# odessa_rev_A.net
KiCad netlist of a schematic drawn in EAGLE
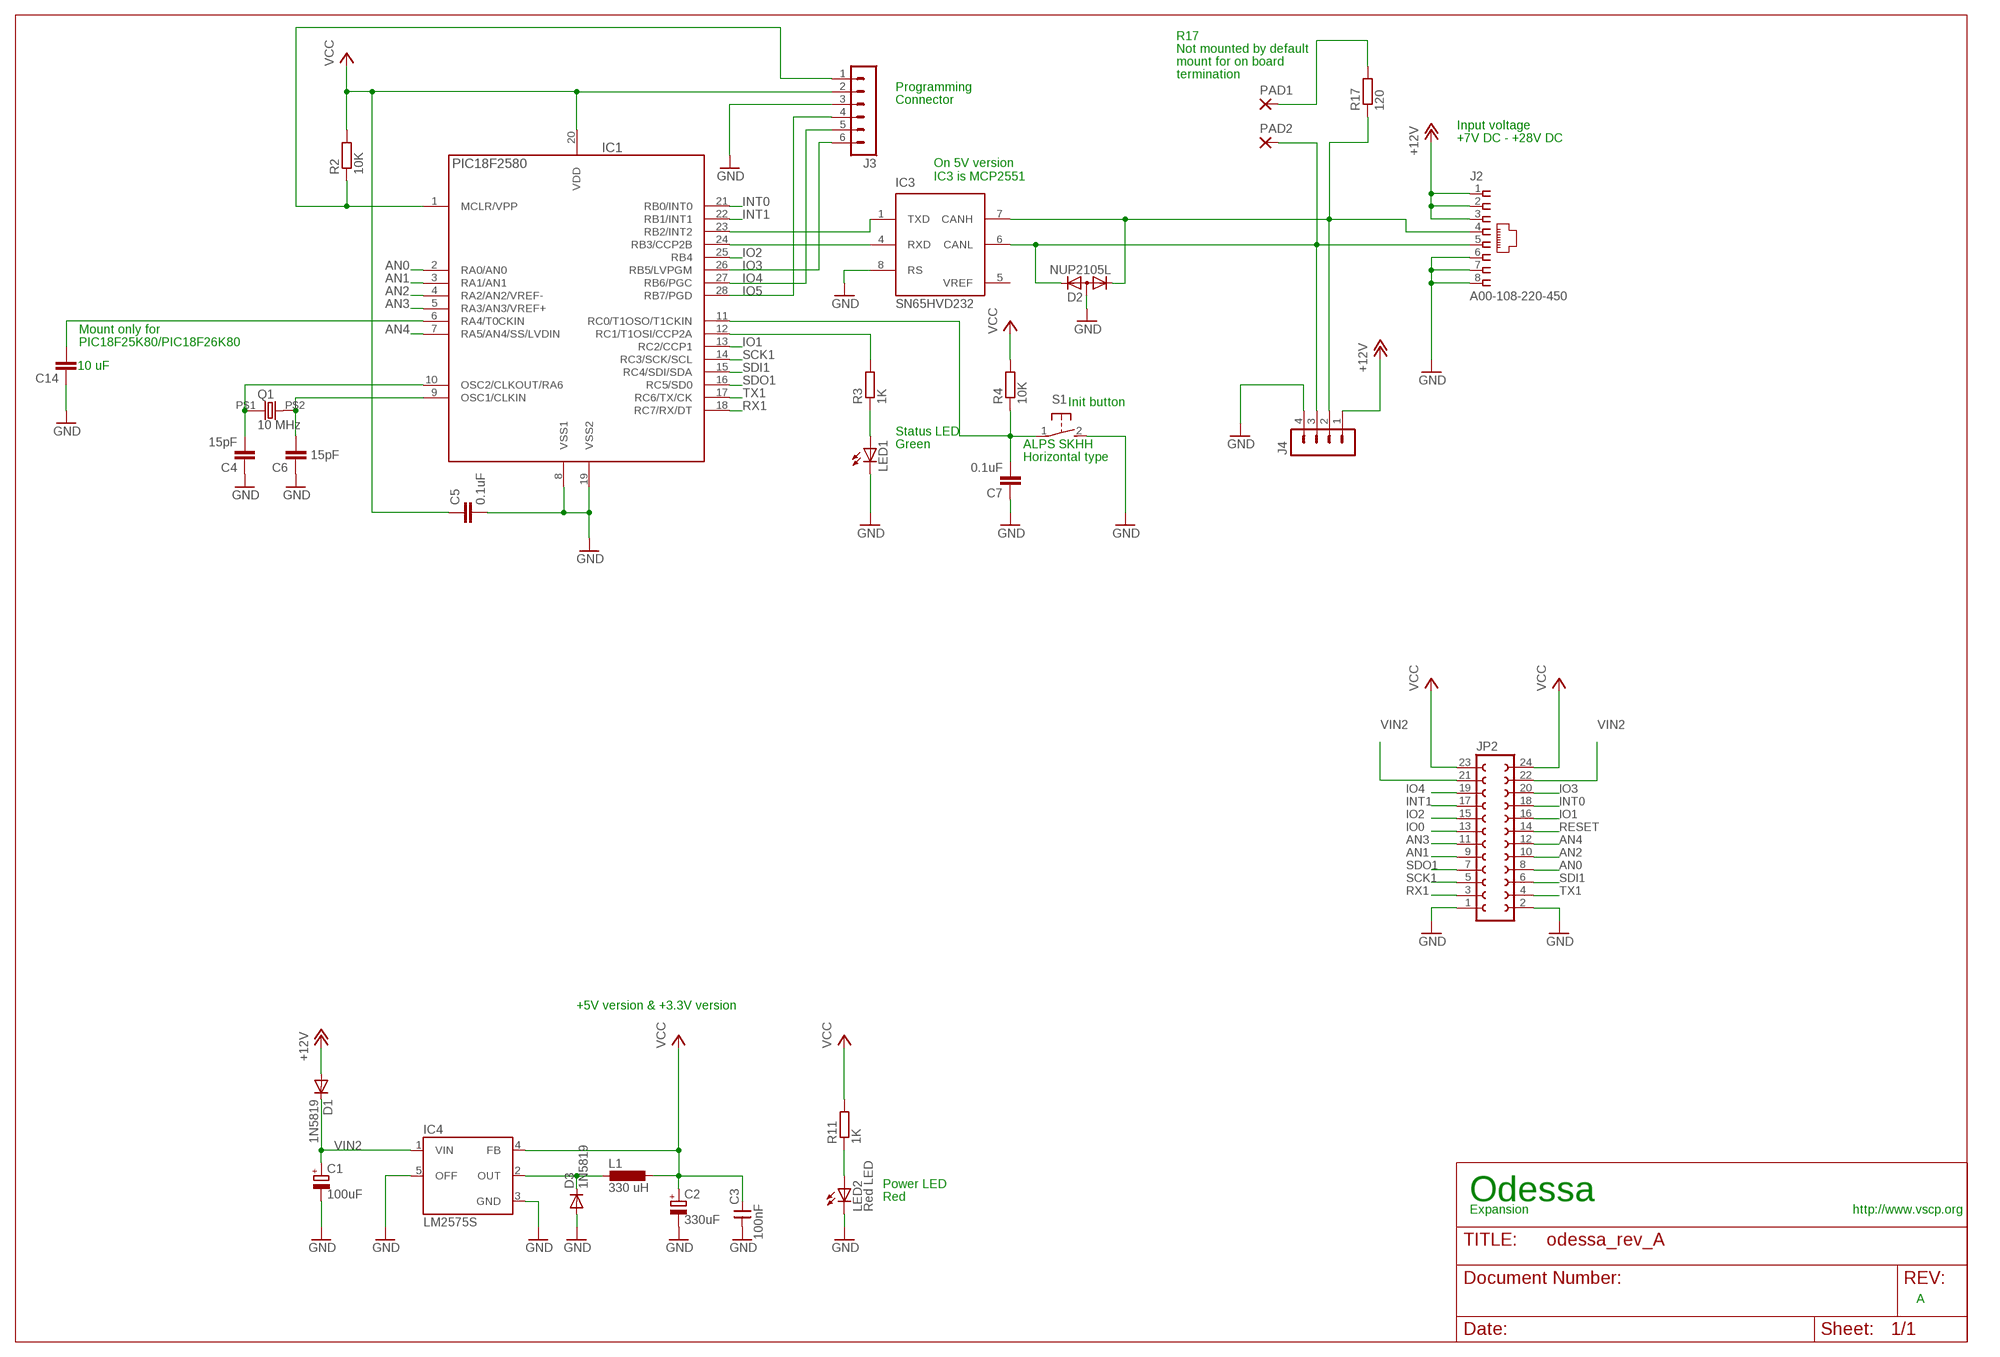
[diagram p0: schematic, sheet 1]

(export (version "E")
  (design (tool "Eeschema 10.0.6"))
  (components
    (comp (ref "C1")
      (value "100uF")
      (footprint "eagle-import:PANASONIC_D")
      (libsource (lib "eagle-import") (part "CPOL-EUD"))
    )
    (comp (ref "C2")
      (value "330uF")
      (footprint "eagle-import:PANASONIC_D")
      (libsource (lib "eagle-import") (part "CPOL-EUD"))
    )
    (comp (ref "C3")
      (value "100nF")
      (footprint "eagle-import:0805")
      (libsource (lib "eagle-import") (part "CNP-0805"))
    )
    (comp (ref "C4")
      (value "15pF")
      (footprint "eagle-import:C0805")
      (libsource (lib "eagle-import") (part "C-EUC0805"))
    )
    (comp (ref "C5")
      (value "0.1uF")
      (footprint "eagle-import:C0805")
      (libsource (lib "eagle-import") (part "C-EUC0805"))
    )
    (comp (ref "C6")
      (value "15pF")
      (footprint "eagle-import:C0805")
      (libsource (lib "eagle-import") (part "C-EUC0805"))
    )
    (comp (ref "C7")
      (value "0.1uF")
      (footprint "eagle-import:C0805")
      (libsource (lib "eagle-import") (part "C-EUC0805"))
    )
    (comp (ref "C14")
      (value "10 uF")
      (footprint "eagle-import:C0805")
      (libsource (lib "eagle-import") (part "C-EUC0805"))
    )
    (comp (ref "D1")
      (value "1N5819")
      (footprint "eagle-import:SOD123")
      (libsource (lib "eagle-import") (part "DIODE-SOD123"))
    )
    (comp (ref "D2")
      (value "NUP2105L")
      (footprint "eagle-import:SOT23")
      (libsource (lib "eagle-import") (part "DIODE-2CA|ACSOT23"))
    )
    (comp (ref "D3")
      (value "1N5819")
      (footprint "eagle-import:SOD123")
      (libsource (lib "eagle-import") (part "DIODE-SOD123"))
    )
    (comp (ref "IC1")
      (value "PIC18F2580")
      (footprint "eagle-import:SO28")
      (libsource (lib "eagle-import") (part "PIC18F252-?I/SOL"))
    )
    (comp (ref "IC3")
      (value "SN65HVD232")
      (footprint "eagle-import:SO-08")
      (libsource (lib "eagle-import") (part "MCP2551SN"))
    )
    (comp (ref "IC4")
      (value "LM2575S")
      (footprint "eagle-import:TO263-5")
      (libsource (lib "eagle-import") (part "LM2575S"))
    )
    (comp (ref "J2")
      (value "A00-108-220-450")
      (footprint "eagle-import:RJ-45")
      (libsource (lib "eagle-import") (part "A00-108-220-450"))
    )
    (comp (ref "J3")
      (value "MA06-1")
      (footprint "eagle-import:MA06-1")
      (libsource (lib "eagle-import") (part "MA06-1"))
    )
    (comp (ref "J4")
      (value "MA04-1")
      (footprint "eagle-import:MA04-1")
      (libsource (lib "eagle-import") (part "MA04-1"))
    )
    (comp (ref "JP2")
      (value "FE12-2")
      (footprint "eagle-import:FE12-2")
      (libsource (lib "eagle-import") (part "FE12-2"))
    )
    (comp (ref "L1")
      (value "330 uH")
      (footprint "eagle-import:DO3316P")
      (libsource (lib "eagle-import") (part "DO3316P"))
    )
    (comp (ref "LED1")
      (value "LEDCHIP-LED0805")
      (footprint "eagle-import:CHIP-LED0805")
      (libsource (lib "eagle-import") (part "LEDCHIP-LED0805"))
    )
    (comp (ref "LED2")
      (value "Red LED")
      (footprint "eagle-import:CHIP-LED0805")
      (libsource (lib "eagle-import") (part "LEDCHIP-LED0805"))
    )
    (comp (ref "PAD1")
      (value "1,6/0,8")
      (footprint "eagle-import:1,6_0,8")
      (libsource (lib "eagle-import") (part "1,6/0,8"))
    )
    (comp (ref "PAD2")
      (value "1,6/0,8")
      (footprint "eagle-import:1,6_0,8")
      (libsource (lib "eagle-import") (part "1,6/0,8"))
    )
    (comp (ref "Q1")
      (value "10 MHz")
      (footprint "eagle-import:9C")
      (libsource (lib "eagle-import") (part "HC-49S"))
    )
    (comp (ref "R2")
      (value "10K")
      (footprint "eagle-import:R0805")
      (libsource (lib "eagle-import") (part "R-EU_R0805"))
    )
    (comp (ref "R3")
      (value "1K")
      (footprint "eagle-import:R0805")
      (libsource (lib "eagle-import") (part "R-EU_R0805"))
    )
    (comp (ref "R4")
      (value "10K")
      (footprint "eagle-import:R0805")
      (libsource (lib "eagle-import") (part "R-EU_R0805"))
    )
    (comp (ref "R11")
      (value "1K")
      (footprint "eagle-import:R0805")
      (libsource (lib "eagle-import") (part "R-EU_R0805"))
    )
    (comp (ref "R17")
      (value "120")
      (footprint "eagle-import:R0805")
      (libsource (lib "eagle-import") (part "R-EU_R0805"))
    )
    (comp (ref "S1")
      (value "31-XX")
      (footprint "eagle-import:B3F-31XX")
      (fields (field (name "MPN") "B3F-3100"))
      (libsource (lib "eagle-import") (part "31-XX"))
    )
  )
  (nets
    (net (code "1") (name "+12V") (class "Default")
      (node (ref "D1") (pin "A") (pinfunction "A_A") (pintype "passive"))
      (node (ref "J2") (pin "1") (pinfunction "1_1") (pintype "passive"))
      (node (ref "J2") (pin "2") (pinfunction "2_2") (pintype "passive"))
      (node (ref "J2") (pin "3") (pinfunction "3_3") (pintype "passive"))
      (node (ref "J4") (pin "1") (pinfunction "1_1") (pintype "passive"))
    )
    (net (code "2") (name "/AN0") (class "Default")
      (node (ref "IC1") (pin "2") (pinfunction "RA0/AN0_2") (pintype "bidirectional"))
      (node (ref "JP2") (pin "8") (pinfunction "8_8") (pintype "passive"))
    )
    (net (code "3") (name "/AN1") (class "Default")
      (node (ref "IC1") (pin "3") (pinfunction "RA1/AN1_3") (pintype "bidirectional"))
      (node (ref "JP2") (pin "9") (pinfunction "9_9") (pintype "passive"))
    )
    (net (code "4") (name "/AN2") (class "Default")
      (node (ref "IC1") (pin "4") (pinfunction "RA2/AN2/VREF-_4") (pintype "bidirectional"))
      (node (ref "JP2") (pin "10") (pinfunction "10_10") (pintype "passive"))
    )
    (net (code "5") (name "/AN3") (class "Default")
      (node (ref "IC1") (pin "5") (pinfunction "RA3/AN3/VREF+_5") (pintype "bidirectional"))
      (node (ref "JP2") (pin "11") (pinfunction "11_11") (pintype "passive"))
    )
    (net (code "6") (name "/AN4") (class "Default")
      (node (ref "IC1") (pin "7") (pinfunction "RA5/AN4/SS/LVDIN_7") (pintype "bidirectional"))
      (node (ref "JP2") (pin "12") (pinfunction "12_12") (pintype "passive"))
    )
    (net (code "7") (name "/INT0") (class "Default")
      (node (ref "IC1") (pin "21") (pinfunction "RB0/INT0_21") (pintype "bidirectional"))
      (node (ref "JP2") (pin "18") (pinfunction "18_18") (pintype "passive"))
    )
    (net (code "8") (name "/INT1") (class "Default")
      (node (ref "IC1") (pin "22") (pinfunction "RB1/INT1_22") (pintype "bidirectional"))
      (node (ref "JP2") (pin "17") (pinfunction "17_17") (pintype "passive"))
    )
    (net (code "9") (name "/IO0") (class "Default")
      (node (ref "JP2") (pin "13") (pinfunction "13_13") (pintype "passive"))
    )
    (net (code "10") (name "/IO1") (class "Default")
      (node (ref "IC1") (pin "13") (pinfunction "RC2/CCP1_13") (pintype "bidirectional"))
      (node (ref "JP2") (pin "16") (pinfunction "16_16") (pintype "passive"))
    )
    (net (code "11") (name "/IO2") (class "Default")
      (node (ref "IC1") (pin "25") (pinfunction "RB4_25") (pintype "bidirectional"))
      (node (ref "JP2") (pin "15") (pinfunction "15_15") (pintype "passive"))
    )
    (net (code "12") (name "/IO3") (class "Default")
      (node (ref "IC1") (pin "26") (pinfunction "RB5/LVPGM_26") (pintype "bidirectional"))
      (node (ref "J3") (pin "6") (pinfunction "6_6") (pintype "passive"))
      (node (ref "JP2") (pin "20") (pinfunction "20_20") (pintype "passive"))
    )
    (net (code "13") (name "/IO4") (class "Default")
      (node (ref "IC1") (pin "27") (pinfunction "RB6/PGC_27") (pintype "bidirectional"))
      (node (ref "J3") (pin "5") (pinfunction "5_5") (pintype "passive"))
      (node (ref "JP2") (pin "19") (pinfunction "19_19") (pintype "passive"))
    )
    (net (code "14") (name "/IO5") (class "Default")
      (node (ref "IC1") (pin "28") (pinfunction "RB7/PGD_28") (pintype "bidirectional"))
      (node (ref "J3") (pin "4") (pinfunction "4_4") (pintype "passive"))
    )
    (net (code "15") (name "/RESET") (class "Default")
      (node (ref "IC1") (pin "1") (pinfunction "MCLR/VPP_1") (pintype "input"))
      (node (ref "J3") (pin "1") (pinfunction "1_1") (pintype "passive"))
      (node (ref "JP2") (pin "14") (pinfunction "14_14") (pintype "passive"))
      (node (ref "R2") (pin "1") (pinfunction "1_1") (pintype "passive"))
    )
    (net (code "16") (name "/RX1") (class "Default")
      (node (ref "IC1") (pin "18") (pinfunction "RC7/RX/DT_18") (pintype "bidirectional"))
      (node (ref "JP2") (pin "3") (pinfunction "3_3") (pintype "passive"))
    )
    (net (code "17") (name "/SCK1") (class "Default")
      (node (ref "IC1") (pin "14") (pinfunction "RC3/SCK/SCL_14") (pintype "bidirectional"))
      (node (ref "JP2") (pin "5") (pinfunction "5_5") (pintype "passive"))
    )
    (net (code "18") (name "/SDI1") (class "Default")
      (node (ref "IC1") (pin "15") (pinfunction "RC4/SDI/SDA_15") (pintype "bidirectional"))
      (node (ref "JP2") (pin "6") (pinfunction "6_6") (pintype "passive"))
    )
    (net (code "19") (name "/SDO1") (class "Default")
      (node (ref "IC1") (pin "16") (pinfunction "RC5/SD0_16") (pintype "bidirectional"))
      (node (ref "JP2") (pin "7") (pinfunction "7_7") (pintype "passive"))
    )
    (net (code "20") (name "/TX1") (class "Default")
      (node (ref "IC1") (pin "17") (pinfunction "RC6/TX/CK_17") (pintype "bidirectional"))
      (node (ref "JP2") (pin "4") (pinfunction "4_4") (pintype "passive"))
    )
    (net (code "21") (name "/VIN2") (class "Default")
      (node (ref "C1") (pin "+") (pinfunction "+_+") (pintype "passive"))
      (node (ref "D1") (pin "C") (pinfunction "C_C") (pintype "passive"))
      (node (ref "IC4") (pin "1") (pinfunction "VIN_1") (pintype "power_in"))
      (node (ref "JP2") (pin "21") (pinfunction "21_21") (pintype "passive"))
      (node (ref "JP2") (pin "22") (pinfunction "22_22") (pintype "passive"))
    )
    (net (code "22") (name "/VREF") (class "Default")
      (node (ref "IC3") (pin "5") (pinfunction "VREF_5") (pintype "power_in"))
    )
    (net (code "23") (name "GND") (class "Default")
      (node (ref "C1") (pin "-") (pinfunction "-_-") (pintype "passive"))
      (node (ref "C14") (pin "1") (pinfunction "1_1") (pintype "passive"))
      (node (ref "C2") (pin "-") (pinfunction "-_-") (pintype "passive"))
      (node (ref "C3") (pin "1") (pinfunction "1_1") (pintype "passive"))
      (node (ref "C4") (pin "1") (pinfunction "1_1") (pintype "passive"))
      (node (ref "C5") (pin "2") (pinfunction "2_2") (pintype "passive"))
      (node (ref "C6") (pin "1") (pinfunction "1_1") (pintype "passive"))
      (node (ref "C7") (pin "1") (pinfunction "1_1") (pintype "passive"))
      (node (ref "D2") (pin "3") (pinfunction "A_3") (pintype "passive"))
      (node (ref "D3") (pin "A") (pinfunction "A_A") (pintype "passive"))
      (node (ref "IC1") (pin "19") (pinfunction "VSS2_19") (pintype "power_in"))
      (node (ref "IC1") (pin "8") (pinfunction "VSS1_8") (pintype "power_in"))
      (node (ref "IC3") (pin "8") (pinfunction "RS_8") (pintype "input"))
      (node (ref "IC4") (pin "3") (pinfunction "GND_3") (pintype "power_in"))
      (node (ref "IC4") (pin "5") (pinfunction "OFF_5") (pintype "input"))
      (node (ref "J2") (pin "6") (pinfunction "6_6") (pintype "passive"))
      (node (ref "J2") (pin "7") (pinfunction "7_7") (pintype "passive"))
      (node (ref "J2") (pin "8") (pinfunction "8_8") (pintype "passive"))
      (node (ref "J3") (pin "3") (pinfunction "3_3") (pintype "passive"))
      (node (ref "J4") (pin "4") (pinfunction "4_4") (pintype "passive"))
      (node (ref "JP2") (pin "1") (pinfunction "1_1") (pintype "passive"))
      (node (ref "JP2") (pin "2") (pinfunction "2_2") (pintype "passive"))
      (node (ref "LED1") (pin "C") (pinfunction "C_C") (pintype "passive"))
      (node (ref "LED2") (pin "C") (pinfunction "C_C") (pintype "passive"))
      (node (ref "S1") (pin "2") (pinfunction "S_2") (pintype "passive"))
    )
    (net (code "24") (name "Net-(D2-K1)") (class "Default")
      (node (ref "D2") (pin "1") (pinfunction "K1_1") (pintype "passive"))
      (node (ref "IC3") (pin "7") (pinfunction "CANH_7") (pintype "bidirectional"))
      (node (ref "J2") (pin "4") (pinfunction "4_4") (pintype "passive"))
      (node (ref "J4") (pin "2") (pinfunction "2_2") (pintype "passive"))
      (node (ref "R17") (pin "1") (pinfunction "1_1") (pintype "passive"))
    )
    (net (code "25") (name "Net-(D2-K2)") (class "Default")
      (node (ref "D2") (pin "2") (pinfunction "K2_2") (pintype "passive"))
      (node (ref "IC3") (pin "6") (pinfunction "CANL_6") (pintype "bidirectional"))
      (node (ref "J2") (pin "5") (pinfunction "5_5") (pintype "passive"))
      (node (ref "J4") (pin "3") (pinfunction "3_3") (pintype "passive"))
      (node (ref "PAD2") (pin "1") (pinfunction "P_1") (pintype "passive"))
    )
    (net (code "26") (name "Net-(IC1-OSC1{slash}CLKIN)") (class "Default")
      (node (ref "C6") (pin "2") (pinfunction "2_2") (pintype "passive"))
      (node (ref "IC1") (pin "9") (pinfunction "OSC1/CLKIN_9") (pintype "input"))
      (node (ref "Q1") (pin "P$2") (pinfunction "2_P$2") (pintype "passive"))
    )
    (net (code "27") (name "Net-(IC1-OSC2{slash}CLKOUT{slash}RA6)") (class "Default")
      (node (ref "C4") (pin "2") (pinfunction "2_2") (pintype "passive"))
      (node (ref "IC1") (pin "10") (pinfunction "OSC2/CLKOUT/RA6_10") (pintype "output"))
      (node (ref "Q1") (pin "P$1") (pinfunction "1_P$1") (pintype "passive"))
    )
    (net (code "28") (name "Net-(IC1-RA4{slash}T0CKIN)") (class "Default")
      (node (ref "C14") (pin "2") (pinfunction "2_2") (pintype "passive"))
      (node (ref "IC1") (pin "6") (pinfunction "RA4/T0CKIN_6") (pintype "open_collector"))
    )
    (net (code "29") (name "Net-(IC1-RB2{slash}INT2)") (class "Default")
      (node (ref "IC1") (pin "23") (pinfunction "RB2/INT2_23") (pintype "bidirectional"))
      (node (ref "IC3") (pin "1") (pinfunction "TXD_1") (pintype "input"))
    )
    (net (code "30") (name "Net-(IC1-RB3{slash}CCP2B)") (class "Default")
      (node (ref "IC1") (pin "24") (pinfunction "RB3/CCP2B_24") (pintype "bidirectional"))
      (node (ref "IC3") (pin "4") (pinfunction "RXD_4") (pintype "output"))
    )
    (net (code "31") (name "Net-(IC1-RC0{slash}T1OSO{slash}T1CKIN)") (class "Default")
      (node (ref "C7") (pin "2") (pinfunction "2_2") (pintype "passive"))
      (node (ref "IC1") (pin "11") (pinfunction "RC0/T1OSO/T1CKIN_11") (pintype "bidirectional"))
      (node (ref "R4") (pin "1") (pinfunction "1_1") (pintype "passive"))
      (node (ref "S1") (pin "1") (pinfunction "P_1") (pintype "passive"))
    )
    (net (code "32") (name "Net-(IC1-RC1{slash}T1OSI{slash}CCP2A)") (class "Default")
      (node (ref "IC1") (pin "12") (pinfunction "RC1/T1OSI/CCP2A_12") (pintype "bidirectional"))
      (node (ref "R3") (pin "2") (pinfunction "2_2") (pintype "passive"))
    )
    (net (code "33") (name "Net-(IC4-OUT)") (class "Default")
      (node (ref "D3") (pin "C") (pinfunction "C_C") (pintype "passive"))
      (node (ref "IC4") (pin "2") (pinfunction "OUT_2") (pintype "output"))
      (node (ref "L1") (pin "1") (pinfunction "1_1") (pintype "passive"))
    )
    (net (code "34") (name "Net-(LED1-PadA)") (class "Default")
      (node (ref "LED1") (pin "A") (pinfunction "A_A") (pintype "passive"))
      (node (ref "R3") (pin "1") (pinfunction "1_1") (pintype "passive"))
    )
    (net (code "35") (name "Net-(LED2-PadA)") (class "Default")
      (node (ref "LED2") (pin "A") (pinfunction "A_A") (pintype "passive"))
      (node (ref "R11") (pin "1") (pinfunction "1_1") (pintype "passive"))
    )
    (net (code "36") (name "Net-(PAD1-P)") (class "Default")
      (node (ref "PAD1") (pin "1") (pinfunction "P_1") (pintype "passive"))
      (node (ref "R17") (pin "2") (pinfunction "2_2") (pintype "passive"))
    )
    (net (code "37") (name "VCC") (class "Default")
      (node (ref "C2") (pin "+") (pinfunction "+_+") (pintype "passive"))
      (node (ref "C3") (pin "2") (pinfunction "2_2") (pintype "passive"))
      (node (ref "C5") (pin "1") (pinfunction "1_1") (pintype "passive"))
      (node (ref "IC1") (pin "20") (pinfunction "VDD_20") (pintype "power_in"))
      (node (ref "IC4") (pin "4") (pinfunction "FB_4") (pintype "input"))
      (node (ref "J3") (pin "2") (pinfunction "2_2") (pintype "passive"))
      (node (ref "JP2") (pin "23") (pinfunction "23_23") (pintype "passive"))
      (node (ref "JP2") (pin "24") (pinfunction "24_24") (pintype "passive"))
      (node (ref "L1") (pin "2") (pinfunction "2_2") (pintype "passive"))
      (node (ref "R11") (pin "2") (pinfunction "2_2") (pintype "passive"))
      (node (ref "R2") (pin "2") (pinfunction "2_2") (pintype "passive"))
      (node (ref "R4") (pin "2") (pinfunction "2_2") (pintype "passive"))
    )
  )
)
